# curve-tracer-trial.net
KiCad netlist of a schematic drawn in EAGLE
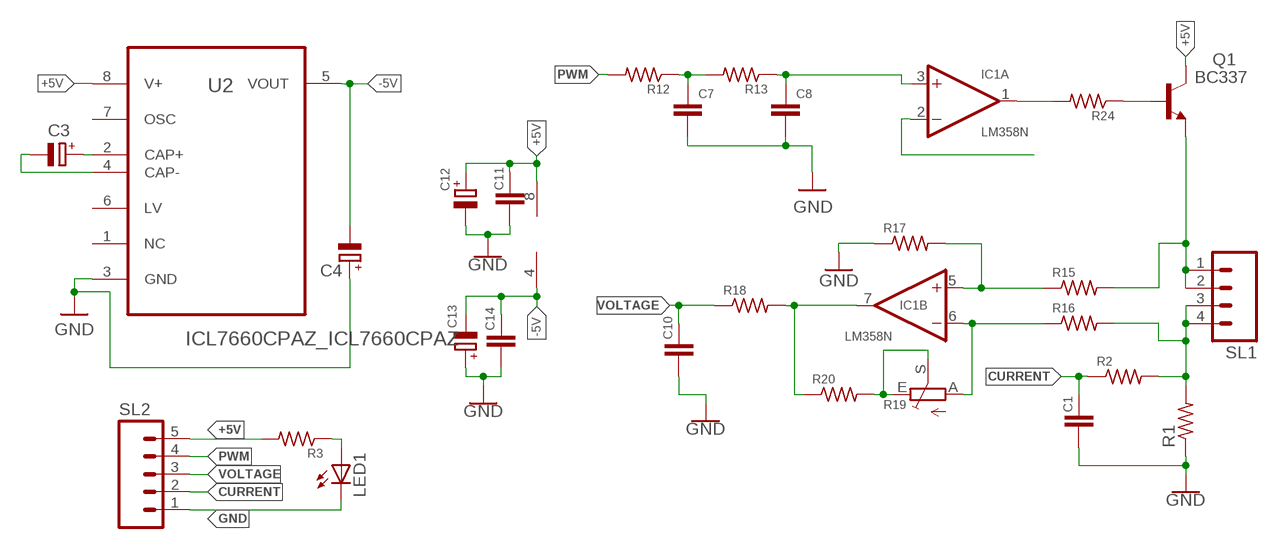
[diagram p0: schematic, sheet 1]

(export (version "E")
  (design (tool "Eeschema 10.0.6"))
  (components
    (comp (ref "C1")
      (value "C-EU025-025X050")
      (footprint "eagle-import:C025-025X050")
      (libsource (lib "eagle-import") (part "C-EU025-025X050"))
    )
    (comp (ref "C3")
      (value "CPOL-EUTT2D5")
      (footprint "eagle-import:TT2D5")
      (libsource (lib "eagle-import") (part "CPOL-EUTT2D5"))
    )
    (comp (ref "C4")
      (value "CPOL-EUTT2D5")
      (footprint "eagle-import:TT2D5")
      (libsource (lib "eagle-import") (part "CPOL-EUTT2D5"))
    )
    (comp (ref "C7")
      (value "C-EU025-025X050")
      (footprint "eagle-import:C025-025X050")
      (libsource (lib "eagle-import") (part "C-EU025-025X050"))
    )
    (comp (ref "C8")
      (value "C-EU025-025X050")
      (footprint "eagle-import:C025-025X050")
      (libsource (lib "eagle-import") (part "C-EU025-025X050"))
    )
    (comp (ref "C10")
      (value "C-EU025-025X050")
      (footprint "eagle-import:C025-025X050")
      (libsource (lib "eagle-import") (part "C-EU025-025X050"))
    )
    (comp (ref "C11")
      (value "C-EU025-025X050")
      (footprint "eagle-import:C025-025X050")
      (libsource (lib "eagle-import") (part "C-EU025-025X050"))
    )
    (comp (ref "C12")
      (value "CPOL-EUTT2D5")
      (footprint "eagle-import:TT2D5")
      (libsource (lib "eagle-import") (part "CPOL-EUTT2D5"))
    )
    (comp (ref "C13")
      (value "CPOL-EUTT2D5")
      (footprint "eagle-import:TT2D5")
      (libsource (lib "eagle-import") (part "CPOL-EUTT2D5"))
    )
    (comp (ref "C14")
      (value "C-EU025-025X050")
      (footprint "eagle-import:C025-025X050")
      (libsource (lib "eagle-import") (part "C-EU025-025X050"))
    )
    (comp (ref "IC1")
      (value "LM358N")
      (footprint "eagle-import:DIL08")
      (libsource (lib "eagle-import") (part "LM358N"))
    )
    (comp (ref "LED1")
      (value "LED3MM")
      (footprint "eagle-import:LED3MM")
      (libsource (lib "eagle-import") (part "LED3MM"))
    )
    (comp (ref "Q1")
      (value "BC337")
      (footprint "eagle-import:TO92")
      (libsource (lib "eagle-import") (part "BC337"))
    )
    (comp (ref "R1")
      (value "RESISTOR0207/10")
      (footprint "eagle-import:0207_10")
      (libsource (lib "eagle-import") (part "RESISTOR0207/10"))
    )
    (comp (ref "R2")
      (value "R-US_0204/7")
      (footprint "eagle-import:0204_7")
      (libsource (lib "eagle-import") (part "R-US_0204/7"))
    )
    (comp (ref "R3")
      (value "R-US_0204/7")
      (footprint "eagle-import:0204_7")
      (libsource (lib "eagle-import") (part "R-US_0204/7"))
    )
    (comp (ref "R12")
      (value "R-US_0204/7")
      (footprint "eagle-import:0204_7")
      (libsource (lib "eagle-import") (part "R-US_0204/7"))
    )
    (comp (ref "R13")
      (value "R-US_0204/7")
      (footprint "eagle-import:0204_7")
      (libsource (lib "eagle-import") (part "R-US_0204/7"))
    )
    (comp (ref "R15")
      (value "R-US_0204/7")
      (footprint "eagle-import:0204_7")
      (libsource (lib "eagle-import") (part "R-US_0204/7"))
    )
    (comp (ref "R16")
      (value "R-US_0204/7")
      (footprint "eagle-import:0204_7")
      (libsource (lib "eagle-import") (part "R-US_0204/7"))
    )
    (comp (ref "R17")
      (value "R-US_0204/7")
      (footprint "eagle-import:0204_7")
      (libsource (lib "eagle-import") (part "R-US_0204/7"))
    )
    (comp (ref "R18")
      (value "R-US_0204/7")
      (footprint "eagle-import:0204_7")
      (libsource (lib "eagle-import") (part "R-US_0204/7"))
    )
    (comp (ref "R19")
      (value "TRIM_EU-RJ9W")
      (footprint "eagle-import:RJ9W")
      (libsource (lib "eagle-import") (part "TRIM_EU-RJ9W"))
    )
    (comp (ref "R20")
      (value "R-US_0204/7")
      (footprint "eagle-import:0204_7")
      (libsource (lib "eagle-import") (part "R-US_0204/7"))
    )
    (comp (ref "R24")
      (value "R-US_0204/7")
      (footprint "eagle-import:0204_7")
      (libsource (lib "eagle-import") (part "R-US_0204/7"))
    )
    (comp (ref "SL1")
      (value "M04")
      (footprint "eagle-import:04P")
      (libsource (lib "eagle-import") (part "M04"))
    )
    (comp (ref "SL2")
      (value "M05")
      (footprint "eagle-import:05P")
      (libsource (lib "eagle-import") (part "M05"))
    )
    (comp (ref "U2")
      (value "ICL7660CPAZ_ICL7660CPAZ")
      (footprint "eagle-import:ICL7660CPAZ_DIP254P762X533-8")
      (fields (field (name "MF") "Renesas Electronics") (field (name "MP") "ICL7660CPAZ"))
      (libsource (lib "eagle-import") (part "ICL7660CPAZ_ICL7660CPAZ"))
    )
  )
  (nets
    (net (code "1") (name "+5V") (class "Default")
      (node (ref "C11") (pin "1") (pinfunction "1_1") (pintype "passive"))
      (node (ref "C12") (pin "+") (pinfunction "+_+") (pintype "passive"))
      (node (ref "IC1") (pin "8") (pinfunction "V+_8") (pintype "power_in"))
      (node (ref "Q1") (pin "3") (pinfunction "C_3") (pintype "passive"))
      (node (ref "R3") (pin "2") (pinfunction "2_2") (pintype "passive"))
      (node (ref "SL2") (pin "5") (pinfunction "5_5") (pintype "passive"))
      (node (ref "U2") (pin "8") (pinfunction "V+_8") (pintype "power_in"))
    )
    (net (code "2") (name "-5V") (class "Default")
      (node (ref "C13") (pin "-") (pinfunction "-_-") (pintype "passive"))
      (node (ref "C14") (pin "1") (pinfunction "1_1") (pintype "passive"))
      (node (ref "C4") (pin "-") (pinfunction "-_-") (pintype "passive"))
      (node (ref "IC1") (pin "4") (pinfunction "V-_4") (pintype "power_in"))
      (node (ref "U2") (pin "5") (pinfunction "VOUT_5") (pintype "output"))
    )
    (net (code "3") (name "CURRENT") (class "Default")
      (node (ref "C1") (pin "1") (pinfunction "1_1") (pintype "passive"))
      (node (ref "R2") (pin "1") (pinfunction "1_1") (pintype "passive"))
      (node (ref "SL2") (pin "2") (pinfunction "2_2") (pintype "passive"))
    )
    (net (code "4") (name "GND") (class "Default")
      (node (ref "C1") (pin "2") (pinfunction "2_2") (pintype "passive"))
      (node (ref "C10") (pin "2") (pinfunction "2_2") (pintype "passive"))
      (node (ref "C11") (pin "2") (pinfunction "2_2") (pintype "passive"))
      (node (ref "C12") (pin "-") (pinfunction "-_-") (pintype "passive"))
      (node (ref "C13") (pin "+") (pinfunction "+_+") (pintype "passive"))
      (node (ref "C14") (pin "2") (pinfunction "2_2") (pintype "passive"))
      (node (ref "C4") (pin "+") (pinfunction "+_+") (pintype "passive"))
      (node (ref "C7") (pin "2") (pinfunction "2_2") (pintype "passive"))
      (node (ref "C8") (pin "2") (pinfunction "2_2") (pintype "passive"))
      (node (ref "LED1") (pin "K") (pinfunction "C_K") (pintype "passive"))
      (node (ref "R1") (pin "1") (pinfunction "1_1") (pintype "passive"))
      (node (ref "R17") (pin "1") (pinfunction "1_1") (pintype "passive"))
      (node (ref "SL2") (pin "1") (pinfunction "1_1") (pintype "passive"))
      (node (ref "U2") (pin "3") (pinfunction "GND_3") (pintype "passive"))
    )
    (net (code "5") (name "Net-(C7-Pad1)") (class "Default")
      (node (ref "C7") (pin "1") (pinfunction "1_1") (pintype "passive"))
      (node (ref "R12") (pin "1") (pinfunction "1_1") (pintype "passive"))
      (node (ref "R13") (pin "2") (pinfunction "2_2") (pintype "passive"))
    )
    (net (code "6") (name "Net-(IC1A-+IN)") (class "Default")
      (node (ref "C8") (pin "1") (pinfunction "1_1") (pintype "passive"))
      (node (ref "IC1") (pin "3") (pinfunction "+IN_3") (pintype "input"))
      (node (ref "R13") (pin "1") (pinfunction "1_1") (pintype "passive"))
    )
    (net (code "7") (name "Net-(IC1A-OUT)") (class "Default")
      (node (ref "IC1") (pin "1") (pinfunction "OUT_1") (pintype "output"))
      (node (ref "R24") (pin "2") (pinfunction "2_2") (pintype "passive"))
    )
    (net (code "8") (name "Net-(IC1B-+IN)") (class "Default")
      (node (ref "IC1") (pin "5") (pinfunction "+IN_5") (pintype "input"))
      (node (ref "R15") (pin "1") (pinfunction "1_1") (pintype "passive"))
      (node (ref "R17") (pin "2") (pinfunction "2_2") (pintype "passive"))
    )
    (net (code "9") (name "Net-(IC1B--IN)") (class "Default")
      (node (ref "IC1") (pin "6") (pinfunction "-IN_6") (pintype "input"))
      (node (ref "R16") (pin "1") (pinfunction "1_1") (pintype "passive"))
      (node (ref "R19") (pin "A") (pinfunction "A_A") (pintype "passive"))
    )
    (net (code "10") (name "Net-(IC1B-OUT)") (class "Default")
      (node (ref "IC1") (pin "7") (pinfunction "OUT_7") (pintype "output"))
      (node (ref "R18") (pin "2") (pinfunction "2_2") (pintype "passive"))
      (node (ref "R20") (pin "1") (pinfunction "1_1") (pintype "passive"))
    )
    (net (code "11") (name "Net-(LED1-PadA)") (class "Default")
      (node (ref "LED1") (pin "A") (pinfunction "A_A") (pintype "passive"))
      (node (ref "R3") (pin "1") (pinfunction "1_1") (pintype "passive"))
    )
    (net (code "12") (name "Net-(Q1-B)") (class "Default")
      (node (ref "Q1") (pin "2") (pinfunction "B_2") (pintype "passive"))
      (node (ref "R24") (pin "1") (pinfunction "1_1") (pintype "passive"))
    )
    (net (code "13") (name "Net-(Q1-E)") (class "Default")
      (node (ref "Q1") (pin "1") (pinfunction "E_1") (pintype "passive"))
      (node (ref "R15") (pin "2") (pinfunction "2_2") (pintype "passive"))
      (node (ref "SL1") (pin "1") (pinfunction "1_1") (pintype "passive"))
      (node (ref "SL1") (pin "2") (pinfunction "2_2") (pintype "passive"))
    )
    (net (code "14") (name "Net-(R1-Pad2)") (class "Default")
      (node (ref "R1") (pin "2") (pinfunction "2_2") (pintype "passive"))
      (node (ref "R16") (pin "2") (pinfunction "2_2") (pintype "passive"))
      (node (ref "R2") (pin "2") (pinfunction "2_2") (pintype "passive"))
      (node (ref "SL1") (pin "3") (pinfunction "3_3") (pintype "passive"))
      (node (ref "SL1") (pin "4") (pinfunction "4_4") (pintype "passive"))
    )
    (net (code "15") (name "Net-(R19-PadE)") (class "Default")
      (node (ref "R19") (pin "E") (pinfunction "E_E") (pintype "passive"))
      (node (ref "R19") (pin "S") (pinfunction "S_S") (pintype "passive"))
      (node (ref "R20") (pin "2") (pinfunction "2_2") (pintype "passive"))
    )
    (net (code "16") (name "Net-(U2-CAP+)") (class "Default")
      (node (ref "C3") (pin "+") (pinfunction "+_+") (pintype "passive"))
      (node (ref "U2") (pin "2") (pinfunction "CAP+_2") (pintype "input"))
    )
    (net (code "17") (name "Net-(U2-CAP-)") (class "Default")
      (node (ref "C3") (pin "-") (pinfunction "-_-") (pintype "passive"))
      (node (ref "U2") (pin "4") (pinfunction "CAP-_4") (pintype "input"))
    )
    (net (code "18") (name "PWM") (class "Default")
      (node (ref "R12") (pin "2") (pinfunction "2_2") (pintype "passive"))
      (node (ref "SL2") (pin "4") (pinfunction "4_4") (pintype "passive"))
    )
    (net (code "19") (name "VOLTAGE") (class "Default")
      (node (ref "C10") (pin "1") (pinfunction "1_1") (pintype "passive"))
      (node (ref "R18") (pin "1") (pinfunction "1_1") (pintype "passive"))
      (node (ref "SL2") (pin "3") (pinfunction "3_3") (pintype "passive"))
    )
    (net (code "20") (name "unconnected-(IC1A--IN-Pad2)") (class "Default")
      (node (ref "IC1") (pin "2") (pinfunction "-IN_2") (pintype "input"))
    )
    (net (code "21") (name "unconnected-(U2-LV-Pad6)") (class "Default")
      (node (ref "U2") (pin "6") (pinfunction "LV_6") (pintype "passive"))
    )
    (net (code "22") (name "unconnected-(U2-NC-Pad1)") (class "Default")
      (node (ref "U2") (pin "1") (pinfunction "NC_1") (pintype "no_connect"))
    )
    (net (code "23") (name "unconnected-(U2-OSC-Pad7)") (class "Default")
      (node (ref "U2") (pin "7") (pinfunction "OSC_7") (pintype "input"))
    )
  )
)
